# MAX44008_Breakout.net
KiCad netlist of a schematic drawn in EAGLE
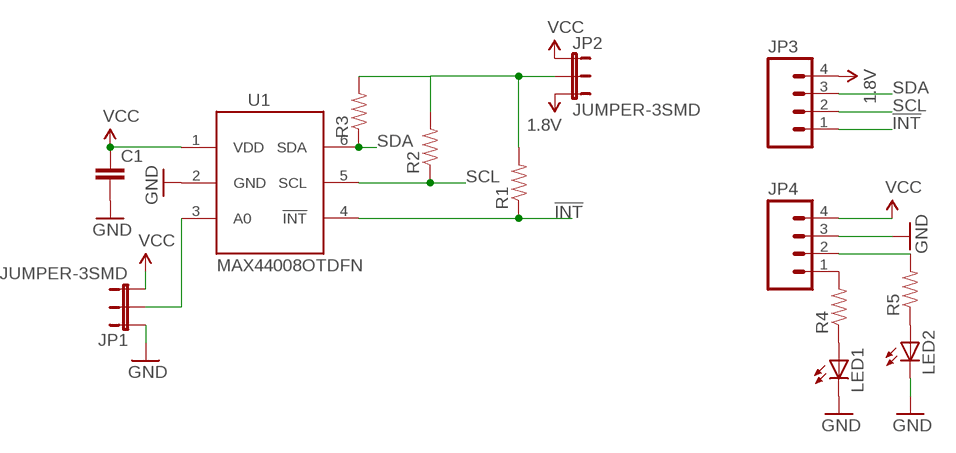
[diagram p0: schematic, sheet 1]

(export (version "E")
  (design (tool "Eeschema 10.0.6"))
  (components
    (comp (ref "C1")
      (value "CAP0603-CAP")
      (footprint "eagle-import:0603-CAP")
      (libsource (lib "eagle-import") (part "CAP0603-CAP"))
    )
    (comp (ref "JP1")
      (value "JUMPER-3SMD")
      (footprint "eagle-import:SJ_3")
      (libsource (lib "eagle-import") (part "JUMPER-3SMD"))
    )
    (comp (ref "JP2")
      (value "JUMPER-3SMD")
      (footprint "eagle-import:SJ_3")
      (libsource (lib "eagle-import") (part "JUMPER-3SMD"))
    )
    (comp (ref "JP3")
      (value "M04PTH")
      (footprint "eagle-import:1X04")
      (libsource (lib "eagle-import") (part "M04PTH"))
    )
    (comp (ref "JP4")
      (value "M04PTH")
      (footprint "eagle-import:1X04")
      (libsource (lib "eagle-import") (part "M04PTH"))
    )
    (comp (ref "LED1")
      (value "LED0603")
      (footprint "eagle-import:LED-0603")
      (libsource (lib "eagle-import") (part "LED0603"))
    )
    (comp (ref "LED2")
      (value "LED0603")
      (footprint "eagle-import:LED-0603")
      (libsource (lib "eagle-import") (part "LED0603"))
    )
    (comp (ref "R1")
      (value "RESISTOR0603-RES")
      (footprint "eagle-import:0603-RES")
      (libsource (lib "eagle-import") (part "RESISTOR0603-RES"))
    )
    (comp (ref "R2")
      (value "RESISTOR0603-RES")
      (footprint "eagle-import:0603-RES")
      (libsource (lib "eagle-import") (part "RESISTOR0603-RES"))
    )
    (comp (ref "R3")
      (value "RESISTOR0603-RES")
      (footprint "eagle-import:0603-RES")
      (libsource (lib "eagle-import") (part "RESISTOR0603-RES"))
    )
    (comp (ref "R4")
      (value "RESISTOR0603-RES")
      (footprint "eagle-import:0603-RES")
      (libsource (lib "eagle-import") (part "RESISTOR0603-RES"))
    )
    (comp (ref "R5")
      (value "RESISTOR0603-RES")
      (footprint "eagle-import:0603-RES")
      (libsource (lib "eagle-import") (part "RESISTOR0603-RES"))
    )
    (comp (ref "U1")
      (value "MAX44008OTDFN")
      (footprint "eagle-import:MAX44008")
      (libsource (lib "eagle-import") (part "MAX44008OTDFN"))
    )
  )
  (nets
    (net (code "1") (name "/SCL") (class "Default")
      (node (ref "JP3") (pin "2") (pinfunction "2_2") (pintype "passive"))
      (node (ref "R2") (pin "1") (pinfunction "1_1") (pintype "passive"))
      (node (ref "U1") (pin "5") (pinfunction "SCL_5") (pintype "bidirectional"))
    )
    (net (code "2") (name "/SDA") (class "Default")
      (node (ref "JP3") (pin "3") (pinfunction "3_3") (pintype "passive"))
      (node (ref "R3") (pin "1") (pinfunction "1_1") (pintype "passive"))
      (node (ref "U1") (pin "6") (pinfunction "SDA_6") (pintype "bidirectional"))
    )
    (net (code "3") (name "/~{INT}") (class "Default")
      (node (ref "JP3") (pin "1") (pinfunction "1_1") (pintype "passive"))
      (node (ref "R1") (pin "1") (pinfunction "1_1") (pintype "passive"))
      (node (ref "U1") (pin "4") (pinfunction "~{INT}_4") (pintype "bidirectional"))
    )
    (net (code "4") (name "1.8V") (class "Default")
      (node (ref "JP2") (pin "3") (pinfunction "3_3") (pintype "passive"))
      (node (ref "JP3") (pin "4") (pinfunction "4_4") (pintype "passive"))
    )
    (net (code "5") (name "GND") (class "Default")
      (node (ref "C1") (pin "2") (pinfunction "2_2") (pintype "passive"))
      (node (ref "JP1") (pin "1") (pinfunction "1_1") (pintype "passive"))
      (node (ref "JP4") (pin "3") (pinfunction "3_3") (pintype "passive"))
      (node (ref "LED1") (pin "C") (pinfunction "C_C") (pintype "passive"))
      (node (ref "LED2") (pin "C") (pinfunction "C_C") (pintype "passive"))
      (node (ref "U1") (pin "2") (pinfunction "GND_2") (pintype "bidirectional"))
    )
    (net (code "6") (name "Net-(JP2-Pad2)") (class "Default")
      (node (ref "JP2") (pin "2") (pinfunction "2_2") (pintype "passive"))
      (node (ref "R1") (pin "2") (pinfunction "2_2") (pintype "passive"))
      (node (ref "R2") (pin "2") (pinfunction "2_2") (pintype "passive"))
      (node (ref "R3") (pin "2") (pinfunction "2_2") (pintype "passive"))
    )
    (net (code "7") (name "Net-(JP4-Pad1)") (class "Default")
      (node (ref "JP4") (pin "1") (pinfunction "1_1") (pintype "passive"))
      (node (ref "R4") (pin "2") (pinfunction "2_2") (pintype "passive"))
    )
    (net (code "8") (name "Net-(JP4-Pad2)") (class "Default")
      (node (ref "JP4") (pin "2") (pinfunction "2_2") (pintype "passive"))
      (node (ref "R5") (pin "2") (pinfunction "2_2") (pintype "passive"))
    )
    (net (code "9") (name "Net-(LED1-PadA)") (class "Default")
      (node (ref "LED1") (pin "A") (pinfunction "A_A") (pintype "passive"))
      (node (ref "R4") (pin "1") (pinfunction "1_1") (pintype "passive"))
    )
    (net (code "10") (name "Net-(LED2-PadA)") (class "Default")
      (node (ref "LED2") (pin "A") (pinfunction "A_A") (pintype "passive"))
      (node (ref "R5") (pin "1") (pinfunction "1_1") (pintype "passive"))
    )
    (net (code "11") (name "Net-(U1-A0)") (class "Default")
      (node (ref "JP1") (pin "2") (pinfunction "2_2") (pintype "passive"))
      (node (ref "U1") (pin "3") (pinfunction "A0_3") (pintype "bidirectional"))
    )
    (net (code "12") (name "VCC") (class "Default")
      (node (ref "C1") (pin "1") (pinfunction "1_1") (pintype "passive"))
      (node (ref "JP1") (pin "3") (pinfunction "3_3") (pintype "passive"))
      (node (ref "JP2") (pin "1") (pinfunction "1_1") (pintype "passive"))
      (node (ref "JP4") (pin "4") (pinfunction "4_4") (pintype "passive"))
      (node (ref "U1") (pin "1") (pinfunction "VDD_1") (pintype "bidirectional"))
    )
  )
)
